# muxpmod.net
KiCad netlist of a schematic drawn in EAGLE
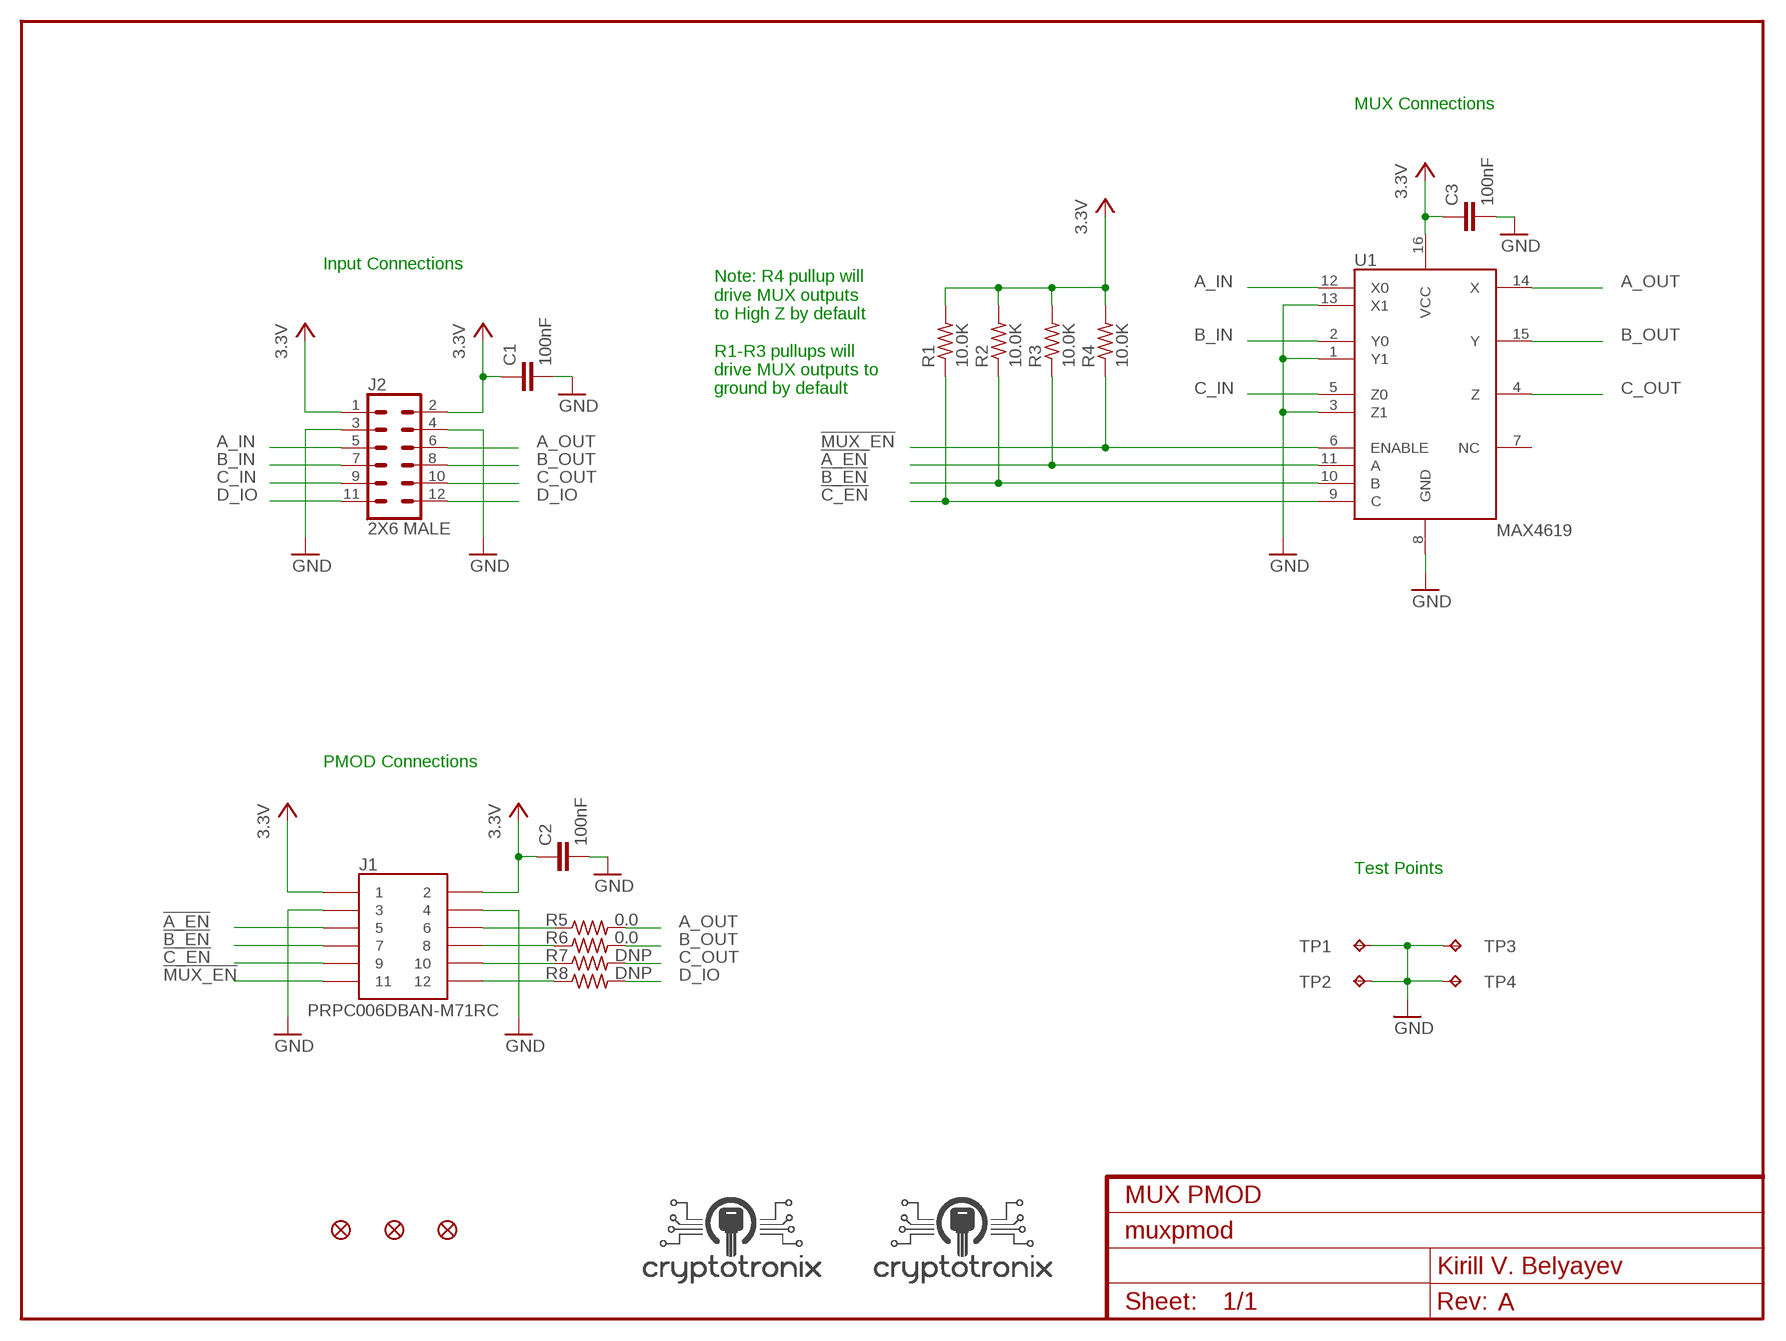
[diagram p0: schematic, sheet 1]

(export (version "E")
  (design (tool "Eeschema 10.0.6"))
  (components
    (comp (ref "C1")
      (value "100nF")
      (footprint "eagle-import:C0603")
      (libsource (lib "eagle-import") (part "C-EUC0603"))
    )
    (comp (ref "C2")
      (value "100nF")
      (footprint "eagle-import:C0603")
      (libsource (lib "eagle-import") (part "C-EUC0603"))
    )
    (comp (ref "C3")
      (value "100nF")
      (footprint "eagle-import:C0603")
      (libsource (lib "eagle-import") (part "C-EUC0603"))
    )
    (comp (ref "FD1")
      (value "FIDUCIALUFIDUCIAL")
      (footprint "eagle-import:MICRO-FIDUCIAL")
      (libsource (lib "eagle-import") (part "FIDUCIALUFIDUCIAL"))
    )
    (comp (ref "FD2")
      (value "FIDUCIALUFIDUCIAL")
      (footprint "eagle-import:MICRO-FIDUCIAL")
      (libsource (lib "eagle-import") (part "FIDUCIALUFIDUCIAL"))
    )
    (comp (ref "FD3")
      (value "FIDUCIALUFIDUCIAL")
      (footprint "eagle-import:MICRO-FIDUCIAL")
      (libsource (lib "eagle-import") (part "FIDUCIALUFIDUCIAL"))
    )
    (comp (ref "J1")
      (value "PRPC006DBAN-M71RC")
      (footprint "eagle-import:PRPC006DBAN-M71RC")
      (fields (field (name "MANUFACTURER") "Sullins"))
      (libsource (lib "eagle-import") (part "PRPC006DBAN-M71RC"))
    )
    (comp (ref "J2")
      (value "2X6 MALE")
      (footprint "eagle-import:2X6")
      (libsource (lib "eagle-import") (part "CONN_06X2PTH_FEMALE"))
    )
    (comp (ref "LOGO1")
      (value "CRYPTOTRONIX_LOGO_S")
      (footprint "eagle-import:CRYPTOTRONIX_LOGO_S")
      (libsource (lib "eagle-import") (part "CRYPTOTRONIX_LOGO_S"))
    )
    (comp (ref "LOGO2")
      (value "CRYPTOTRONIX_LOGO_S")
      (footprint "eagle-import:CRYPTOTRONIX_LOGO_S")
      (libsource (lib "eagle-import") (part "CRYPTOTRONIX_LOGO_S"))
    )
    (comp (ref "R1")
      (value "10.0K")
      (footprint "eagle-import:R0603")
      (libsource (lib "eagle-import") (part "R-US_R0603"))
    )
    (comp (ref "R2")
      (value "10.0K")
      (footprint "eagle-import:R0603")
      (libsource (lib "eagle-import") (part "R-US_R0603"))
    )
    (comp (ref "R3")
      (value "10.0K")
      (footprint "eagle-import:R0603")
      (libsource (lib "eagle-import") (part "R-US_R0603"))
    )
    (comp (ref "R4")
      (value "10.0K")
      (footprint "eagle-import:R0603")
      (libsource (lib "eagle-import") (part "R-US_R0603"))
    )
    (comp (ref "R5")
      (value "0.0")
      (footprint "eagle-import:R0603")
      (libsource (lib "eagle-import") (part "R-US_R0603"))
    )
    (comp (ref "R6")
      (value "0.0")
      (footprint "eagle-import:R0603")
      (libsource (lib "eagle-import") (part "R-US_R0603"))
    )
    (comp (ref "R7")
      (value "DNP")
      (footprint "eagle-import:R0603")
      (libsource (lib "eagle-import") (part "R-US_R0603"))
    )
    (comp (ref "R8")
      (value "DNP")
      (footprint "eagle-import:R0603")
      (libsource (lib "eagle-import") (part "R-US_R0603"))
    )
    (comp (ref "TP1")
      (value "TEST-POINT-SM")
      (footprint "eagle-import:5015")
      (fields (field (name "MAN-PART_NUM") "5015") (field (name "MANUFACTURER") "KEYSTONE"))
      (libsource (lib "eagle-import") (part "TEST-POINT-SM"))
    )
    (comp (ref "TP2")
      (value "TEST-POINT-SM")
      (footprint "eagle-import:5015")
      (fields (field (name "MAN-PART_NUM") "5015") (field (name "MANUFACTURER") "KEYSTONE"))
      (libsource (lib "eagle-import") (part "TEST-POINT-SM"))
    )
    (comp (ref "TP3")
      (value "TEST-POINT-SM")
      (footprint "eagle-import:5015")
      (fields (field (name "MAN-PART_NUM") "5015") (field (name "MANUFACTURER") "KEYSTONE"))
      (libsource (lib "eagle-import") (part "TEST-POINT-SM"))
    )
    (comp (ref "TP4")
      (value "TEST-POINT-SM")
      (footprint "eagle-import:5015")
      (fields (field (name "MAN-PART_NUM") "5015") (field (name "MANUFACTURER") "KEYSTONE"))
      (libsource (lib "eagle-import") (part "TEST-POINT-SM"))
    )
    (comp (ref "U1")
      (value "MAX4619")
      (footprint "eagle-import:16SOIC")
      (fields (field (name "MAN-PART_NUM") "MAX4619CSE+") (field (name "MANUFACTURER") "Maxim Integrated"))
      (libsource (lib "eagle-import") (part "MAX4619"))
    )
  )
  (nets
    (net (code "1") (name "/A_IN") (class "Default")
      (node (ref "J2") (pin "5") (pinfunction "5_5") (pintype "passive"))
      (node (ref "U1") (pin "12") (pinfunction "X0_12") (pintype "bidirectional"))
    )
    (net (code "2") (name "/A_OUT") (class "Default")
      (node (ref "J2") (pin "6") (pinfunction "6_6") (pintype "passive"))
      (node (ref "R5") (pin "2") (pinfunction "2_2") (pintype "passive"))
      (node (ref "U1") (pin "14") (pinfunction "X_14") (pintype "bidirectional"))
    )
    (net (code "3") (name "/B_IN") (class "Default")
      (node (ref "J2") (pin "7") (pinfunction "7_7") (pintype "passive"))
      (node (ref "U1") (pin "2") (pinfunction "Y0_2") (pintype "bidirectional"))
    )
    (net (code "4") (name "/B_OUT") (class "Default")
      (node (ref "J2") (pin "8") (pinfunction "8_8") (pintype "passive"))
      (node (ref "R6") (pin "2") (pinfunction "2_2") (pintype "passive"))
      (node (ref "U1") (pin "15") (pinfunction "Y_15") (pintype "bidirectional"))
    )
    (net (code "5") (name "/C_IN") (class "Default")
      (node (ref "J2") (pin "9") (pinfunction "9_9") (pintype "passive"))
      (node (ref "U1") (pin "5") (pinfunction "Z0_5") (pintype "bidirectional"))
    )
    (net (code "6") (name "/C_OUT") (class "Default")
      (node (ref "J2") (pin "10") (pinfunction "10_10") (pintype "passive"))
      (node (ref "R7") (pin "2") (pinfunction "2_2") (pintype "passive"))
      (node (ref "U1") (pin "4") (pinfunction "Z_4") (pintype "bidirectional"))
    )
    (net (code "7") (name "/D_IO") (class "Default")
      (node (ref "J2") (pin "11") (pinfunction "11_11") (pintype "passive"))
      (node (ref "J2") (pin "12") (pinfunction "12_12") (pintype "passive"))
      (node (ref "R8") (pin "2") (pinfunction "2_2") (pintype "passive"))
    )
    (net (code "8") (name "/~{A_EN}") (class "Default")
      (node (ref "J1") (pin "5") (pinfunction "5_5") (pintype "bidirectional"))
      (node (ref "R3") (pin "1") (pinfunction "1_1") (pintype "passive"))
      (node (ref "U1") (pin "11") (pinfunction "A_11") (pintype "bidirectional"))
    )
    (net (code "9") (name "/~{B_EN}") (class "Default")
      (node (ref "J1") (pin "7") (pinfunction "7_7") (pintype "bidirectional"))
      (node (ref "R2") (pin "1") (pinfunction "1_1") (pintype "passive"))
      (node (ref "U1") (pin "10") (pinfunction "B_10") (pintype "bidirectional"))
    )
    (net (code "10") (name "/~{C_EN}") (class "Default")
      (node (ref "J1") (pin "9") (pinfunction "9_9") (pintype "bidirectional"))
      (node (ref "R1") (pin "1") (pinfunction "1_1") (pintype "passive"))
      (node (ref "U1") (pin "9") (pinfunction "C_9") (pintype "bidirectional"))
    )
    (net (code "11") (name "/~{MUX_EN}") (class "Default")
      (node (ref "J1") (pin "11") (pinfunction "11_11") (pintype "bidirectional"))
      (node (ref "R4") (pin "1") (pinfunction "1_1") (pintype "passive"))
      (node (ref "U1") (pin "6") (pinfunction "ENABLE_6") (pintype "bidirectional"))
    )
    (net (code "12") (name "3.3V") (class "Default")
      (node (ref "C1") (pin "1") (pinfunction "1_1") (pintype "passive"))
      (node (ref "C2") (pin "1") (pinfunction "1_1") (pintype "passive"))
      (node (ref "C3") (pin "1") (pinfunction "1_1") (pintype "passive"))
      (node (ref "J1") (pin "1") (pinfunction "1_1") (pintype "bidirectional"))
      (node (ref "J1") (pin "2") (pinfunction "2_2") (pintype "bidirectional"))
      (node (ref "J2") (pin "1") (pinfunction "1_1") (pintype "passive"))
      (node (ref "J2") (pin "2") (pinfunction "2_2") (pintype "passive"))
      (node (ref "R1") (pin "2") (pinfunction "2_2") (pintype "passive"))
      (node (ref "R2") (pin "2") (pinfunction "2_2") (pintype "passive"))
      (node (ref "R3") (pin "2") (pinfunction "2_2") (pintype "passive"))
      (node (ref "R4") (pin "2") (pinfunction "2_2") (pintype "passive"))
      (node (ref "U1") (pin "16") (pinfunction "VCC_16") (pintype "bidirectional"))
    )
    (net (code "13") (name "GND") (class "Default")
      (node (ref "C1") (pin "2") (pinfunction "2_2") (pintype "passive"))
      (node (ref "C2") (pin "2") (pinfunction "2_2") (pintype "passive"))
      (node (ref "C3") (pin "2") (pinfunction "2_2") (pintype "passive"))
      (node (ref "J1") (pin "3") (pinfunction "3_3") (pintype "bidirectional"))
      (node (ref "J1") (pin "4") (pinfunction "4_4") (pintype "bidirectional"))
      (node (ref "J2") (pin "3") (pinfunction "3_3") (pintype "passive"))
      (node (ref "J2") (pin "4") (pinfunction "4_4") (pintype "passive"))
      (node (ref "TP1") (pin "1") (pinfunction "PP_1") (pintype "input"))
      (node (ref "TP2") (pin "1") (pinfunction "PP_1") (pintype "input"))
      (node (ref "TP3") (pin "1") (pinfunction "PP_1") (pintype "input"))
      (node (ref "TP4") (pin "1") (pinfunction "PP_1") (pintype "input"))
      (node (ref "U1") (pin "1") (pinfunction "Y1_1") (pintype "bidirectional"))
      (node (ref "U1") (pin "13") (pinfunction "X1_13") (pintype "bidirectional"))
      (node (ref "U1") (pin "3") (pinfunction "Z1_3") (pintype "bidirectional"))
      (node (ref "U1") (pin "8") (pinfunction "GND_8") (pintype "bidirectional"))
    )
    (net (code "14") (name "Net-(J1-Pad6)") (class "Default")
      (node (ref "J1") (pin "6") (pinfunction "6_6") (pintype "bidirectional"))
      (node (ref "R5") (pin "1") (pinfunction "1_1") (pintype "passive"))
    )
    (net (code "15") (name "Net-(J1-Pad8)") (class "Default")
      (node (ref "J1") (pin "8") (pinfunction "8_8") (pintype "bidirectional"))
      (node (ref "R6") (pin "1") (pinfunction "1_1") (pintype "passive"))
    )
    (net (code "16") (name "Net-(J1-Pad10)") (class "Default")
      (node (ref "J1") (pin "10") (pinfunction "10_10") (pintype "bidirectional"))
      (node (ref "R7") (pin "1") (pinfunction "1_1") (pintype "passive"))
    )
    (net (code "17") (name "Net-(J1-Pad12)") (class "Default")
      (node (ref "J1") (pin "12") (pinfunction "12_12") (pintype "bidirectional"))
      (node (ref "R8") (pin "1") (pinfunction "1_1") (pintype "passive"))
    )
    (net (code "18") (name "unconnected-(U1-NC-Pad7)") (class "Default")
      (node (ref "U1") (pin "7") (pinfunction "NC_7") (pintype "bidirectional"))
    )
  )
)
